# board.net
KiCad netlist of a schematic drawn in EAGLE
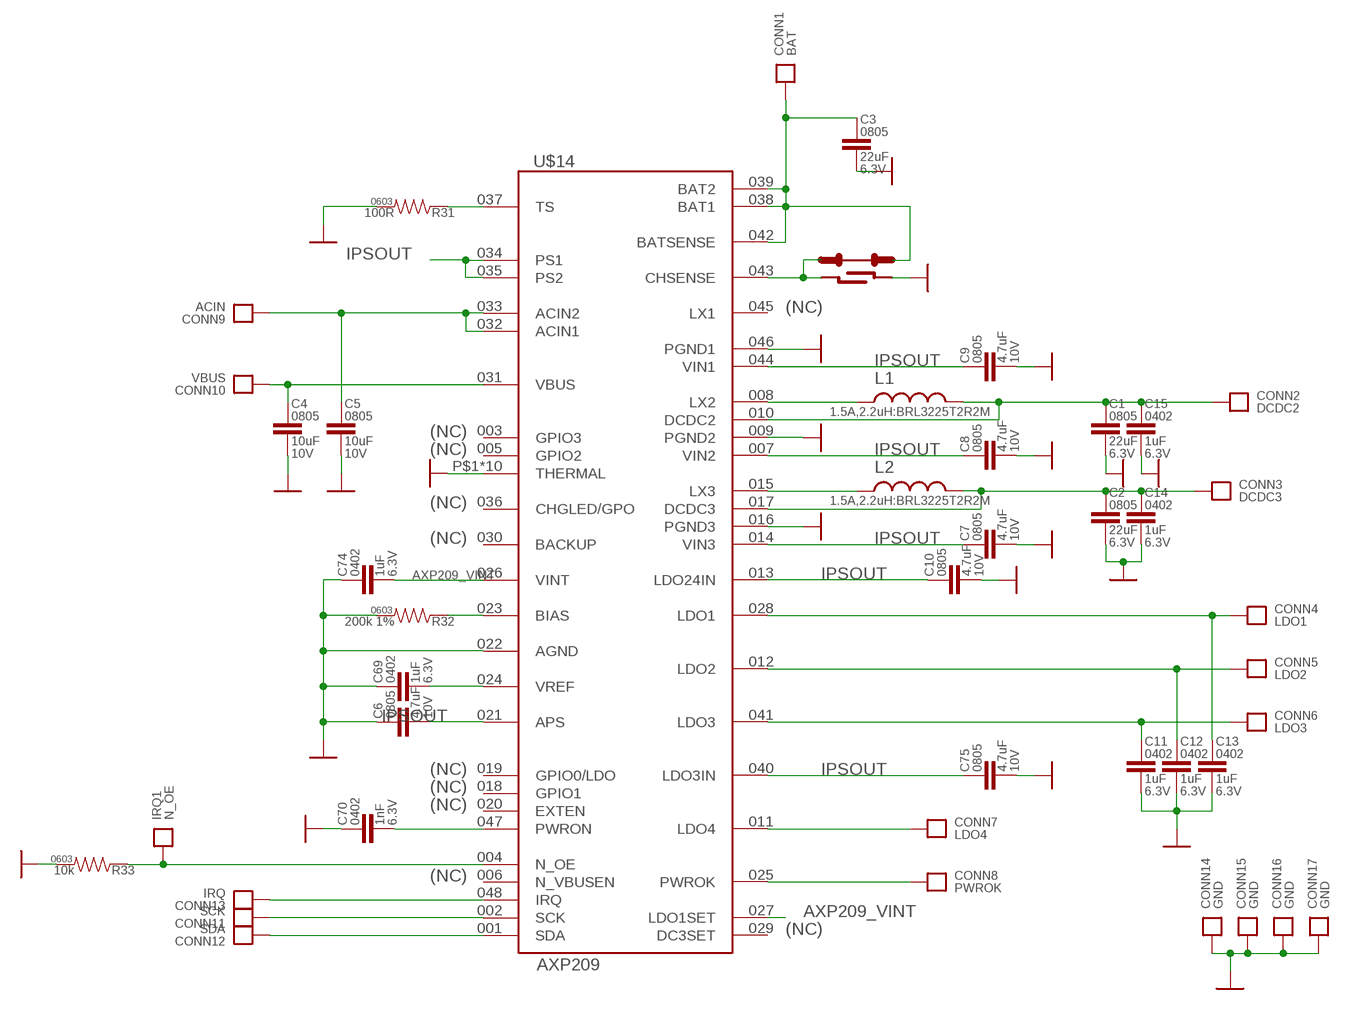
[diagram p0: schematic, sheet 1]

(export (version "E")
  (design (tool "Eeschema 10.0.6"))
  (components
    (comp (ref "C1")
      (value "22uF")
      (footprint "eagle-import:0805")
      (fields (field (name "VOLTAGE") "6.3V"))
      (libsource (lib "eagle-import") (part "CAP0805"))
    )
    (comp (ref "C2")
      (value "22uF")
      (footprint "eagle-import:0805")
      (fields (field (name "VOLTAGE") "6.3V"))
      (libsource (lib "eagle-import") (part "CAP0805"))
    )
    (comp (ref "C3")
      (value "22uF")
      (footprint "eagle-import:0805")
      (fields (field (name "VOLTAGE") "6.3V"))
      (libsource (lib "eagle-import") (part "CAP0805"))
    )
    (comp (ref "C4")
      (value "10uF")
      (footprint "eagle-import:0805")
      (fields (field (name "VOLTAGE") "6.3V") (field (name "VOLTAGE_1") "10V"))
      (libsource (lib "eagle-import") (part "CAP0805"))
    )
    (comp (ref "C5")
      (value "10uF")
      (footprint "eagle-import:0805")
      (fields (field (name "VOLTAGE") "6.3V") (field (name "VOLTAGE_1") "10V"))
      (libsource (lib "eagle-import") (part "CAP0805"))
    )
    (comp (ref "C6")
      (value "4.7uF")
      (footprint "eagle-import:0805")
      (fields (field (name "VOLTAGE") "6.3V") (field (name "VOLTAGE_1") "10V"))
      (libsource (lib "eagle-import") (part "CAP0805"))
    )
    (comp (ref "C7")
      (value "4.7uF")
      (footprint "eagle-import:0805")
      (fields (field (name "VOLTAGE") "6.3V") (field (name "VOLTAGE_1") "10V"))
      (libsource (lib "eagle-import") (part "CAP0805"))
    )
    (comp (ref "C8")
      (value "4.7uF")
      (footprint "eagle-import:0805")
      (fields (field (name "VOLTAGE") "6.3V") (field (name "VOLTAGE_1") "10V"))
      (libsource (lib "eagle-import") (part "CAP0805"))
    )
    (comp (ref "C9")
      (value "4.7uF")
      (footprint "eagle-import:0805")
      (fields (field (name "VOLTAGE") "6.3V") (field (name "VOLTAGE_1") "10V"))
      (libsource (lib "eagle-import") (part "CAP0805"))
    )
    (comp (ref "C10")
      (value "4.7uF")
      (footprint "eagle-import:0805")
      (fields (field (name "VOLTAGE") "6.3V") (field (name "VOLTAGE_1") "10V"))
      (libsource (lib "eagle-import") (part "CAP0805"))
    )
    (comp (ref "C11")
      (value "1uF")
      (footprint "eagle-import:0402-CAP")
      (fields (field (name "VOLTAGE") "6.3V"))
      (libsource (lib "eagle-import") (part "CAP0402-CAP"))
    )
    (comp (ref "C12")
      (value "1uF")
      (footprint "eagle-import:0402-CAP")
      (fields (field (name "VOLTAGE") "6.3V"))
      (libsource (lib "eagle-import") (part "CAP0402-CAP"))
    )
    (comp (ref "C13")
      (value "1uF")
      (footprint "eagle-import:0402-CAP")
      (fields (field (name "VOLTAGE") "6.3V"))
      (libsource (lib "eagle-import") (part "CAP0402-CAP"))
    )
    (comp (ref "C14")
      (value "1uF")
      (footprint "eagle-import:0402-CAP")
      (fields (field (name "VOLTAGE") "6.3V"))
      (libsource (lib "eagle-import") (part "CAP0402-CAP"))
    )
    (comp (ref "C15")
      (value "1uF")
      (footprint "eagle-import:0402-CAP")
      (fields (field (name "VOLTAGE") "6.3V"))
      (libsource (lib "eagle-import") (part "CAP0402-CAP"))
    )
    (comp (ref "C69")
      (value "1uF")
      (footprint "eagle-import:0402-CAP")
      (fields (field (name "VOLTAGE") "6.3V"))
      (libsource (lib "eagle-import") (part "CAP0402-CAP"))
    )
    (comp (ref "C70")
      (value "1nF")
      (footprint "eagle-import:0402-CAP")
      (fields (field (name "VOLTAGE") "6.3V"))
      (libsource (lib "eagle-import") (part "CAP0402-CAP"))
    )
    (comp (ref "C74")
      (value "1uF")
      (footprint "eagle-import:0402-CAP")
      (fields (field (name "VOLTAGE") "6.3V"))
      (libsource (lib "eagle-import") (part "CAP0402-CAP"))
    )
    (comp (ref "C75")
      (value "4.7uF")
      (footprint "eagle-import:0805")
      (fields (field (name "VOLTAGE") "6.3V") (field (name "VOLTAGE_1") "10V"))
      (libsource (lib "eagle-import") (part "CAP0805"))
    )
    (comp (ref "CONN1")
      (value "BAT")
      (footprint "eagle-import:HOLE_22AWG")
      (libsource (lib "eagle-import") (part "CONNECTOR22AWG"))
    )
    (comp (ref "CONN2")
      (value "DCDC2")
      (footprint "eagle-import:HOLE_22AWG")
      (libsource (lib "eagle-import") (part "CONNECTOR22AWG"))
    )
    (comp (ref "CONN3")
      (value "DCDC3")
      (footprint "eagle-import:HOLE_22AWG")
      (libsource (lib "eagle-import") (part "CONNECTOR22AWG"))
    )
    (comp (ref "CONN4")
      (value "LDO1")
      (footprint "eagle-import:HOLE_22AWG")
      (libsource (lib "eagle-import") (part "CONNECTOR22AWG"))
    )
    (comp (ref "CONN5")
      (value "LDO2")
      (footprint "eagle-import:HOLE_22AWG")
      (libsource (lib "eagle-import") (part "CONNECTOR22AWG"))
    )
    (comp (ref "CONN6")
      (value "LDO3")
      (footprint "eagle-import:HOLE_22AWG")
      (libsource (lib "eagle-import") (part "CONNECTOR22AWG"))
    )
    (comp (ref "CONN7")
      (value "LDO4")
      (footprint "eagle-import:HOLE_22AWG")
      (libsource (lib "eagle-import") (part "CONNECTOR22AWG"))
    )
    (comp (ref "CONN8")
      (value "PWROK")
      (footprint "eagle-import:HOLE_22AWG")
      (libsource (lib "eagle-import") (part "CONNECTOR22AWG"))
    )
    (comp (ref "CONN9")
      (value "ACIN")
      (footprint "eagle-import:HOLE_22AWG")
      (libsource (lib "eagle-import") (part "CONNECTOR22AWG"))
    )
    (comp (ref "CONN10")
      (value "VBUS")
      (footprint "eagle-import:HOLE_22AWG")
      (libsource (lib "eagle-import") (part "CONNECTOR22AWG"))
    )
    (comp (ref "CONN11")
      (value "SCK")
      (footprint "eagle-import:HOLE_22AWG")
      (libsource (lib "eagle-import") (part "CONNECTOR22AWG"))
    )
    (comp (ref "CONN12")
      (value "SDA")
      (footprint "eagle-import:HOLE_22AWG")
      (libsource (lib "eagle-import") (part "CONNECTOR22AWG"))
    )
    (comp (ref "CONN13")
      (value "IRQ")
      (footprint "eagle-import:HOLE_22AWG")
      (libsource (lib "eagle-import") (part "CONNECTOR22AWG"))
    )
    (comp (ref "CONN14")
      (value "GND")
      (footprint "eagle-import:HOLE_22AWG")
      (libsource (lib "eagle-import") (part "CONNECTOR22AWG"))
    )
    (comp (ref "CONN15")
      (value "GND")
      (footprint "eagle-import:HOLE_22AWG")
      (libsource (lib "eagle-import") (part "CONNECTOR22AWG"))
    )
    (comp (ref "CONN16")
      (value "GND")
      (footprint "eagle-import:HOLE_22AWG")
      (libsource (lib "eagle-import") (part "CONNECTOR22AWG"))
    )
    (comp (ref "CONN17")
      (value "GND")
      (footprint "eagle-import:HOLE_22AWG")
      (libsource (lib "eagle-import") (part "CONNECTOR22AWG"))
    )
    (comp (ref "IRQ1")
      (value "N_OE")
      (footprint "eagle-import:HOLE_22AWG")
      (libsource (lib "eagle-import") (part "CONNECTOR22AWG"))
    )
    (comp (ref "L1")
      (value "1.5A,2.2uH:BRL3225T2R2M")
      (footprint "eagle-import:1206")
      (libsource (lib "eagle-import") (part "INDUCTOR1206"))
    )
    (comp (ref "L2")
      (value "1.5A,2.2uH:BRL3225T2R2M")
      (footprint "eagle-import:1206")
      (libsource (lib "eagle-import") (part "INDUCTOR1206"))
    )
    (comp (ref "R31")
      (value "100R")
      (footprint "eagle-import:0603-RES")
      (libsource (lib "eagle-import") (part "RESISTOR0603"))
    )
    (comp (ref "R32")
      (value "200k 1%")
      (footprint "eagle-import:0603-RES")
      (libsource (lib "eagle-import") (part "RESISTOR0603"))
    )
    (comp (ref "R33")
      (value "10k")
      (footprint "eagle-import:0603-RES")
      (libsource (lib "eagle-import") (part "RESISTOR0603"))
    )
    (comp (ref "SB7")
      (value "SOLDER-BRIDGEOPEN")
      (footprint "eagle-import:SOLDER-BRIDGE-OPEN")
      (libsource (lib "eagle-import") (part "SOLDER-BRIDGEOPEN"))
    )
    (comp (ref "SB8")
      (value "TRACE-CUT")
      (footprint "eagle-import:TRACE-CUT")
      (libsource (lib "eagle-import") (part "TRACE-CUT"))
    )
    (comp (ref "U$14")
      (value "AXP209")
      (footprint "eagle-import:QFN48")
      (libsource (lib "eagle-import") (part "AXP209"))
    )
  )
  (nets
    (net (code "1") (name "/AXP209_VINT") (class "Default")
      (node (ref "C74") (pin "2") (pinfunction "2_2") (pintype "passive"))
      (node (ref "U$14") (pin "026") (pinfunction "VINT_026") (pintype "bidirectional"))
      (node (ref "U$14") (pin "027") (pinfunction "LDO1SET_027") (pintype "bidirectional"))
    )
    (net (code "2") (name "/IPSOUT") (class "Default")
      (node (ref "C10") (pin "1") (pinfunction "1_1") (pintype "passive"))
      (node (ref "C6") (pin "2") (pinfunction "2_2") (pintype "passive"))
      (node (ref "C7") (pin "1") (pinfunction "1_1") (pintype "passive"))
      (node (ref "C75") (pin "1") (pinfunction "1_1") (pintype "passive"))
      (node (ref "C8") (pin "1") (pinfunction "1_1") (pintype "passive"))
      (node (ref "C9") (pin "1") (pinfunction "1_1") (pintype "passive"))
      (node (ref "U$14") (pin "007") (pinfunction "VIN2_007") (pintype "bidirectional"))
      (node (ref "U$14") (pin "013") (pinfunction "LDO24IN_013") (pintype "bidirectional"))
      (node (ref "U$14") (pin "014") (pinfunction "VIN3_014") (pintype "bidirectional"))
      (node (ref "U$14") (pin "021") (pinfunction "APS_021") (pintype "bidirectional"))
      (node (ref "U$14") (pin "034") (pinfunction "PS1_034") (pintype "bidirectional"))
      (node (ref "U$14") (pin "035") (pinfunction "PS2_035") (pintype "bidirectional"))
      (node (ref "U$14") (pin "040") (pinfunction "LDO3IN_040") (pintype "bidirectional"))
      (node (ref "U$14") (pin "044") (pinfunction "VIN1_044") (pintype "bidirectional"))
    )
    (net (code "3") (name "GND") (class "Default")
      (node (ref "C1") (pin "2") (pinfunction "2_2") (pintype "passive"))
      (node (ref "C10") (pin "2") (pinfunction "2_2") (pintype "passive"))
      (node (ref "C11") (pin "2") (pinfunction "2_2") (pintype "passive"))
      (node (ref "C12") (pin "2") (pinfunction "2_2") (pintype "passive"))
      (node (ref "C13") (pin "2") (pinfunction "2_2") (pintype "passive"))
      (node (ref "C14") (pin "2") (pinfunction "2_2") (pintype "passive"))
      (node (ref "C15") (pin "2") (pinfunction "2_2") (pintype "passive"))
      (node (ref "C2") (pin "2") (pinfunction "2_2") (pintype "passive"))
      (node (ref "C3") (pin "2") (pinfunction "2_2") (pintype "passive"))
      (node (ref "C4") (pin "2") (pinfunction "2_2") (pintype "passive"))
      (node (ref "C5") (pin "2") (pinfunction "2_2") (pintype "passive"))
      (node (ref "C6") (pin "1") (pinfunction "1_1") (pintype "passive"))
      (node (ref "C69") (pin "1") (pinfunction "1_1") (pintype "passive"))
      (node (ref "C7") (pin "2") (pinfunction "2_2") (pintype "passive"))
      (node (ref "C70") (pin "1") (pinfunction "1_1") (pintype "passive"))
      (node (ref "C74") (pin "1") (pinfunction "1_1") (pintype "passive"))
      (node (ref "C75") (pin "2") (pinfunction "2_2") (pintype "passive"))
      (node (ref "C8") (pin "2") (pinfunction "2_2") (pintype "passive"))
      (node (ref "C9") (pin "2") (pinfunction "2_2") (pintype "passive"))
      (node (ref "CONN14") (pin "P") (pinfunction "P_P") (pintype "bidirectional"))
      (node (ref "CONN15") (pin "P") (pinfunction "P_P") (pintype "bidirectional"))
      (node (ref "CONN16") (pin "P") (pinfunction "P_P") (pintype "bidirectional"))
      (node (ref "CONN17") (pin "P") (pinfunction "P_P") (pintype "bidirectional"))
      (node (ref "R31") (pin "2") (pinfunction "2_2") (pintype "passive"))
      (node (ref "R32") (pin "2") (pinfunction "2_2") (pintype "passive"))
      (node (ref "R33") (pin "2") (pinfunction "2_2") (pintype "passive"))
      (node (ref "SB7") (pin "L1") (pinfunction "P$1_L1") (pintype "passive"))
      (node (ref "SB7") (pin "L2") (pinfunction "P$1_L2") (pintype "passive"))
      (node (ref "U$14") (pin "009") (pinfunction "PGND2_009") (pintype "bidirectional"))
      (node (ref "U$14") (pin "016") (pinfunction "PGND3_016") (pintype "bidirectional"))
      (node (ref "U$14") (pin "022") (pinfunction "AGND_022") (pintype "bidirectional"))
      (node (ref "U$14") (pin "046") (pinfunction "PGND1_046") (pintype "bidirectional"))
      (node (ref "U$14") (pin "P$1") (pinfunction "THERMAL_P$1") (pintype "bidirectional"))
      (node (ref "U$14") (pin "P$2") (pinfunction "THERMAL_P$2") (pintype "bidirectional"))
      (node (ref "U$14") (pin "P$3") (pinfunction "THERMAL_P$3") (pintype "bidirectional"))
      (node (ref "U$14") (pin "P$4") (pinfunction "THERMAL_P$4") (pintype "bidirectional"))
      (node (ref "U$14") (pin "P$5") (pinfunction "THERMAL_P$5") (pintype "bidirectional"))
      (node (ref "U$14") (pin "P$6") (pinfunction "THERMAL_P$6") (pintype "bidirectional"))
      (node (ref "U$14") (pin "P$7") (pinfunction "THERMAL_P$7") (pintype "bidirectional"))
      (node (ref "U$14") (pin "P$8") (pinfunction "THERMAL_P$8") (pintype "bidirectional"))
      (node (ref "U$14") (pin "P$9") (pinfunction "THERMAL_P$9") (pintype "bidirectional"))
      (node (ref "U$14") (pin "PAD") (pinfunction "THERMAL_PAD") (pintype "bidirectional"))
    )
    (net (code "4") (name "Net-(SB8-P$1)") (class "Default")
      (node (ref "SB7") (pin "R1") (pinfunction "P$2_R1") (pintype "passive"))
      (node (ref "SB7") (pin "R2") (pinfunction "P$2_R2") (pintype "passive"))
      (node (ref "SB8") (pin "L1") (pinfunction "P$1_L1") (pintype "passive"))
      (node (ref "U$14") (pin "043") (pinfunction "CHSENSE_043") (pintype "bidirectional"))
    )
    (net (code "5") (name "Net-(SB8-P$2)") (class "Default")
      (node (ref "C3") (pin "1") (pinfunction "1_1") (pintype "passive"))
      (node (ref "CONN1") (pin "P") (pinfunction "P_P") (pintype "bidirectional"))
      (node (ref "SB8") (pin "R1") (pinfunction "P$2_R1") (pintype "passive"))
      (node (ref "U$14") (pin "038") (pinfunction "BAT1_038") (pintype "bidirectional"))
      (node (ref "U$14") (pin "039") (pinfunction "BAT2_039") (pintype "bidirectional"))
      (node (ref "U$14") (pin "042") (pinfunction "BATSENSE_042") (pintype "bidirectional"))
    )
    (net (code "6") (name "Net-(U$14-ACIN1)") (class "Default")
      (node (ref "C5") (pin "1") (pinfunction "1_1") (pintype "passive"))
      (node (ref "CONN9") (pin "P") (pinfunction "P_P") (pintype "bidirectional"))
      (node (ref "U$14") (pin "032") (pinfunction "ACIN1_032") (pintype "bidirectional"))
      (node (ref "U$14") (pin "033") (pinfunction "ACIN2_033") (pintype "bidirectional"))
    )
    (net (code "7") (name "Net-(U$14-BIAS)") (class "Default")
      (node (ref "R32") (pin "1") (pinfunction "1_1") (pintype "passive"))
      (node (ref "U$14") (pin "023") (pinfunction "BIAS_023") (pintype "bidirectional"))
    )
    (net (code "8") (name "Net-(U$14-DCDC2)") (class "Default")
      (node (ref "C1") (pin "1") (pinfunction "1_1") (pintype "passive"))
      (node (ref "C15") (pin "1") (pinfunction "1_1") (pintype "passive"))
      (node (ref "CONN2") (pin "P") (pinfunction "P_P") (pintype "bidirectional"))
      (node (ref "L1") (pin "2") (pinfunction "2_2") (pintype "passive"))
      (node (ref "U$14") (pin "010") (pinfunction "DCDC2_010") (pintype "bidirectional"))
    )
    (net (code "9") (name "Net-(U$14-DCDC3)") (class "Default")
      (node (ref "C14") (pin "1") (pinfunction "1_1") (pintype "passive"))
      (node (ref "C2") (pin "1") (pinfunction "1_1") (pintype "passive"))
      (node (ref "CONN3") (pin "P") (pinfunction "P_P") (pintype "bidirectional"))
      (node (ref "L2") (pin "2") (pinfunction "2_2") (pintype "passive"))
      (node (ref "U$14") (pin "017") (pinfunction "DCDC3_017") (pintype "bidirectional"))
    )
    (net (code "10") (name "Net-(U$14-IRQ)") (class "Default")
      (node (ref "CONN13") (pin "P") (pinfunction "P_P") (pintype "bidirectional"))
      (node (ref "U$14") (pin "048") (pinfunction "IRQ_048") (pintype "bidirectional"))
    )
    (net (code "11") (name "Net-(U$14-LDO1)") (class "Default")
      (node (ref "C13") (pin "1") (pinfunction "1_1") (pintype "passive"))
      (node (ref "CONN4") (pin "P") (pinfunction "P_P") (pintype "bidirectional"))
      (node (ref "U$14") (pin "028") (pinfunction "LDO1_028") (pintype "bidirectional"))
    )
    (net (code "12") (name "Net-(U$14-LDO2)") (class "Default")
      (node (ref "C12") (pin "1") (pinfunction "1_1") (pintype "passive"))
      (node (ref "CONN5") (pin "P") (pinfunction "P_P") (pintype "bidirectional"))
      (node (ref "U$14") (pin "012") (pinfunction "LDO2_012") (pintype "bidirectional"))
    )
    (net (code "13") (name "Net-(U$14-LDO3)") (class "Default")
      (node (ref "C11") (pin "1") (pinfunction "1_1") (pintype "passive"))
      (node (ref "CONN6") (pin "P") (pinfunction "P_P") (pintype "bidirectional"))
      (node (ref "U$14") (pin "041") (pinfunction "LDO3_041") (pintype "bidirectional"))
    )
    (net (code "14") (name "Net-(U$14-LDO4)") (class "Default")
      (node (ref "CONN7") (pin "P") (pinfunction "P_P") (pintype "bidirectional"))
      (node (ref "U$14") (pin "011") (pinfunction "LDO4_011") (pintype "bidirectional"))
    )
    (net (code "15") (name "Net-(U$14-LX2)") (class "Default")
      (node (ref "L1") (pin "1") (pinfunction "1_1") (pintype "passive"))
      (node (ref "U$14") (pin "008") (pinfunction "LX2_008") (pintype "bidirectional"))
    )
    (net (code "16") (name "Net-(U$14-LX3)") (class "Default")
      (node (ref "L2") (pin "1") (pinfunction "1_1") (pintype "passive"))
      (node (ref "U$14") (pin "015") (pinfunction "LX3_015") (pintype "bidirectional"))
    )
    (net (code "17") (name "Net-(U$14-N_OE)") (class "Default")
      (node (ref "IRQ1") (pin "P") (pinfunction "P_P") (pintype "bidirectional"))
      (node (ref "R33") (pin "1") (pinfunction "1_1") (pintype "passive"))
      (node (ref "U$14") (pin "004") (pinfunction "N_OE_004") (pintype "bidirectional"))
    )
    (net (code "18") (name "Net-(U$14-PWROK)") (class "Default")
      (node (ref "CONN8") (pin "P") (pinfunction "P_P") (pintype "bidirectional"))
      (node (ref "U$14") (pin "025") (pinfunction "PWROK_025") (pintype "bidirectional"))
    )
    (net (code "19") (name "Net-(U$14-PWRON)") (class "Default")
      (node (ref "C70") (pin "2") (pinfunction "2_2") (pintype "passive"))
      (node (ref "U$14") (pin "047") (pinfunction "PWRON_047") (pintype "bidirectional"))
    )
    (net (code "20") (name "Net-(U$14-SCK)") (class "Default")
      (node (ref "CONN11") (pin "P") (pinfunction "P_P") (pintype "bidirectional"))
      (node (ref "U$14") (pin "002") (pinfunction "SCK_002") (pintype "bidirectional"))
    )
    (net (code "21") (name "Net-(U$14-SDA)") (class "Default")
      (node (ref "CONN12") (pin "P") (pinfunction "P_P") (pintype "bidirectional"))
      (node (ref "U$14") (pin "001") (pinfunction "SDA_001") (pintype "bidirectional"))
    )
    (net (code "22") (name "Net-(U$14-TS)") (class "Default")
      (node (ref "R31") (pin "1") (pinfunction "1_1") (pintype "passive"))
      (node (ref "U$14") (pin "037") (pinfunction "TS_037") (pintype "bidirectional"))
    )
    (net (code "23") (name "Net-(U$14-VBUS)") (class "Default")
      (node (ref "C4") (pin "1") (pinfunction "1_1") (pintype "passive"))
      (node (ref "CONN10") (pin "P") (pinfunction "P_P") (pintype "bidirectional"))
      (node (ref "U$14") (pin "031") (pinfunction "VBUS_031") (pintype "bidirectional"))
    )
    (net (code "24") (name "Net-(U$14-VREF)") (class "Default")
      (node (ref "C69") (pin "2") (pinfunction "2_2") (pintype "passive"))
      (node (ref "U$14") (pin "024") (pinfunction "VREF_024") (pintype "bidirectional"))
    )
    (net (code "25") (name "unconnected-(U$14-BACKUP-Pad030)") (class "Default")
      (node (ref "U$14") (pin "030") (pinfunction "BACKUP_030") (pintype "bidirectional"))
    )
    (net (code "26") (name "unconnected-(U$14-CHGLED{slash}GPO-Pad036)") (class "Default")
      (node (ref "U$14") (pin "036") (pinfunction "CHGLED/GPO_036") (pintype "bidirectional"))
    )
    (net (code "27") (name "unconnected-(U$14-DC3SET-Pad029)") (class "Default")
      (node (ref "U$14") (pin "029") (pinfunction "DC3SET_029") (pintype "bidirectional"))
    )
    (net (code "28") (name "unconnected-(U$14-EXTEN-Pad020)") (class "Default")
      (node (ref "U$14") (pin "020") (pinfunction "EXTEN_020") (pintype "bidirectional"))
    )
    (net (code "29") (name "unconnected-(U$14-GPIO0{slash}LDO-Pad019)") (class "Default")
      (node (ref "U$14") (pin "019") (pinfunction "GPIO0/LDO_019") (pintype "bidirectional"))
    )
    (net (code "30") (name "unconnected-(U$14-GPIO1-Pad018)") (class "Default")
      (node (ref "U$14") (pin "018") (pinfunction "GPIO1_018") (pintype "bidirectional"))
    )
    (net (code "31") (name "unconnected-(U$14-GPIO2-Pad005)") (class "Default")
      (node (ref "U$14") (pin "005") (pinfunction "GPIO2_005") (pintype "bidirectional"))
    )
    (net (code "32") (name "unconnected-(U$14-GPIO3-Pad003)") (class "Default")
      (node (ref "U$14") (pin "003") (pinfunction "GPIO3_003") (pintype "bidirectional"))
    )
    (net (code "33") (name "unconnected-(U$14-LX1-Pad045)") (class "Default")
      (node (ref "U$14") (pin "045") (pinfunction "LX1_045") (pintype "bidirectional"))
    )
    (net (code "34") (name "unconnected-(U$14-N_VBUSEN-Pad006)") (class "Default")
      (node (ref "U$14") (pin "006") (pinfunction "N_VBUSEN_006") (pintype "bidirectional"))
    )
  )
)
